# 03-ToF.net
KiCad netlist of a schematic drawn in EAGLE
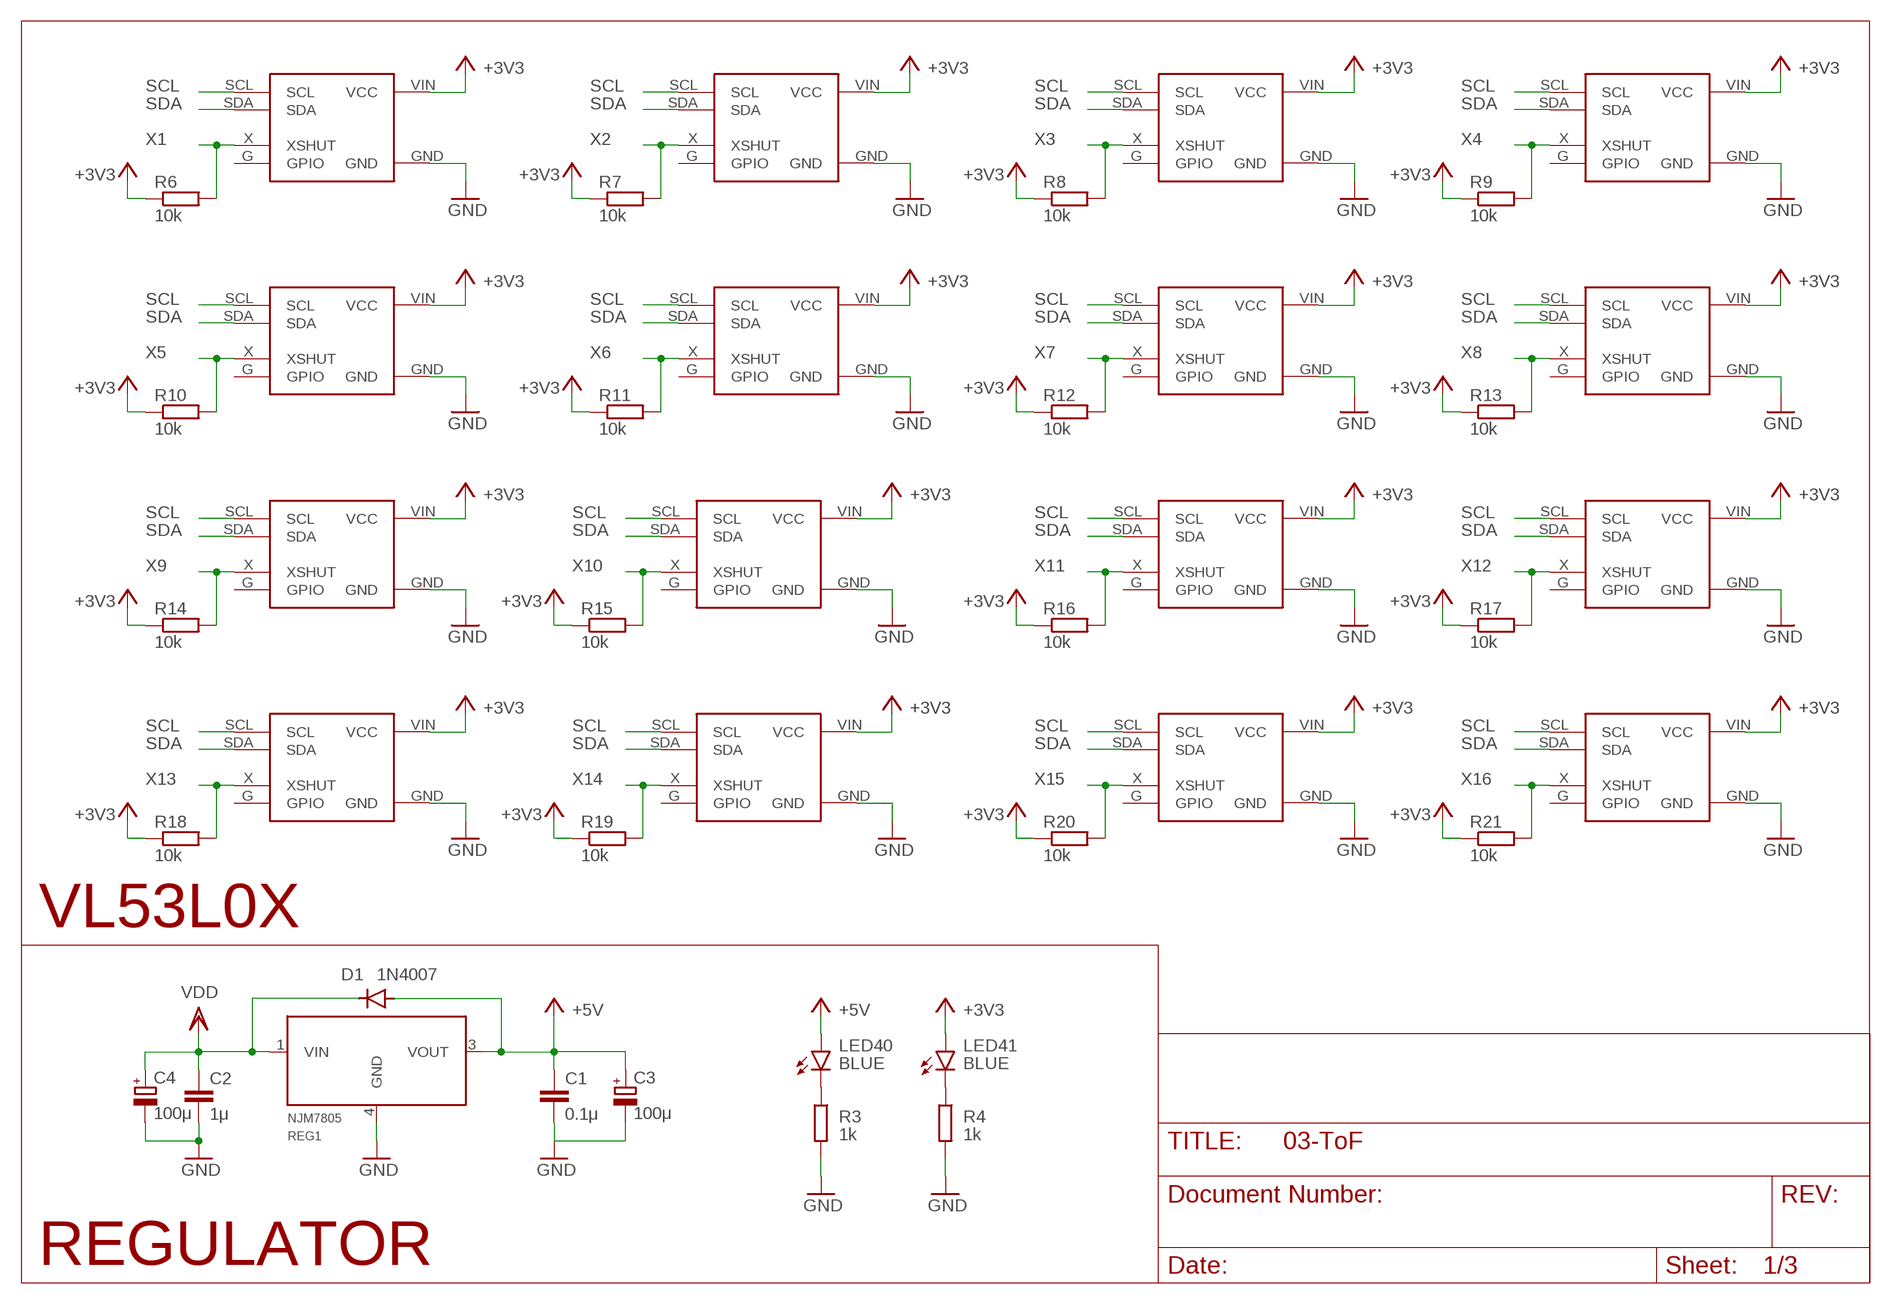
[diagram p0: schematic, sheet 1]
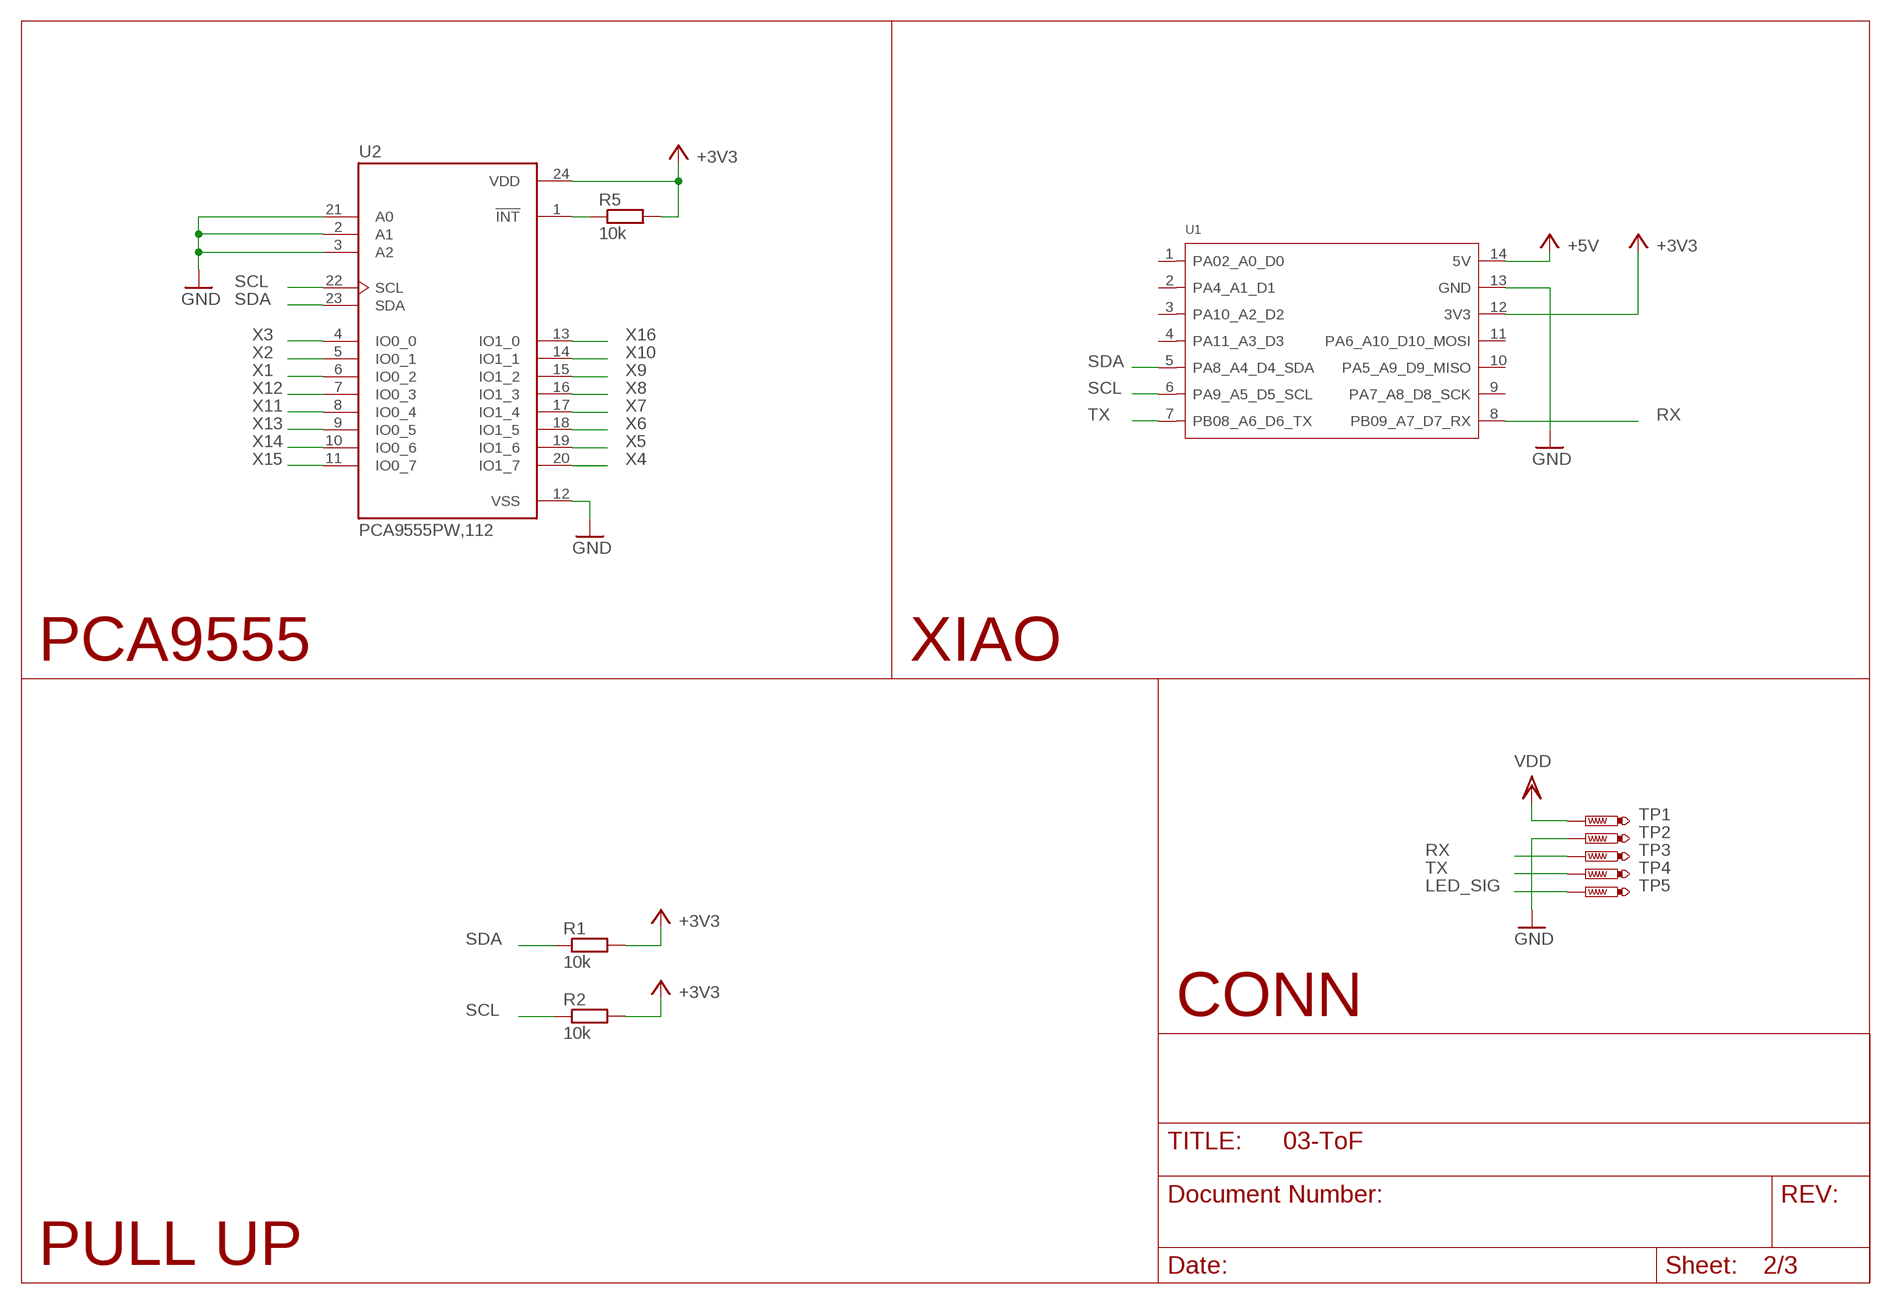
[diagram p1: schematic, sheet 2]
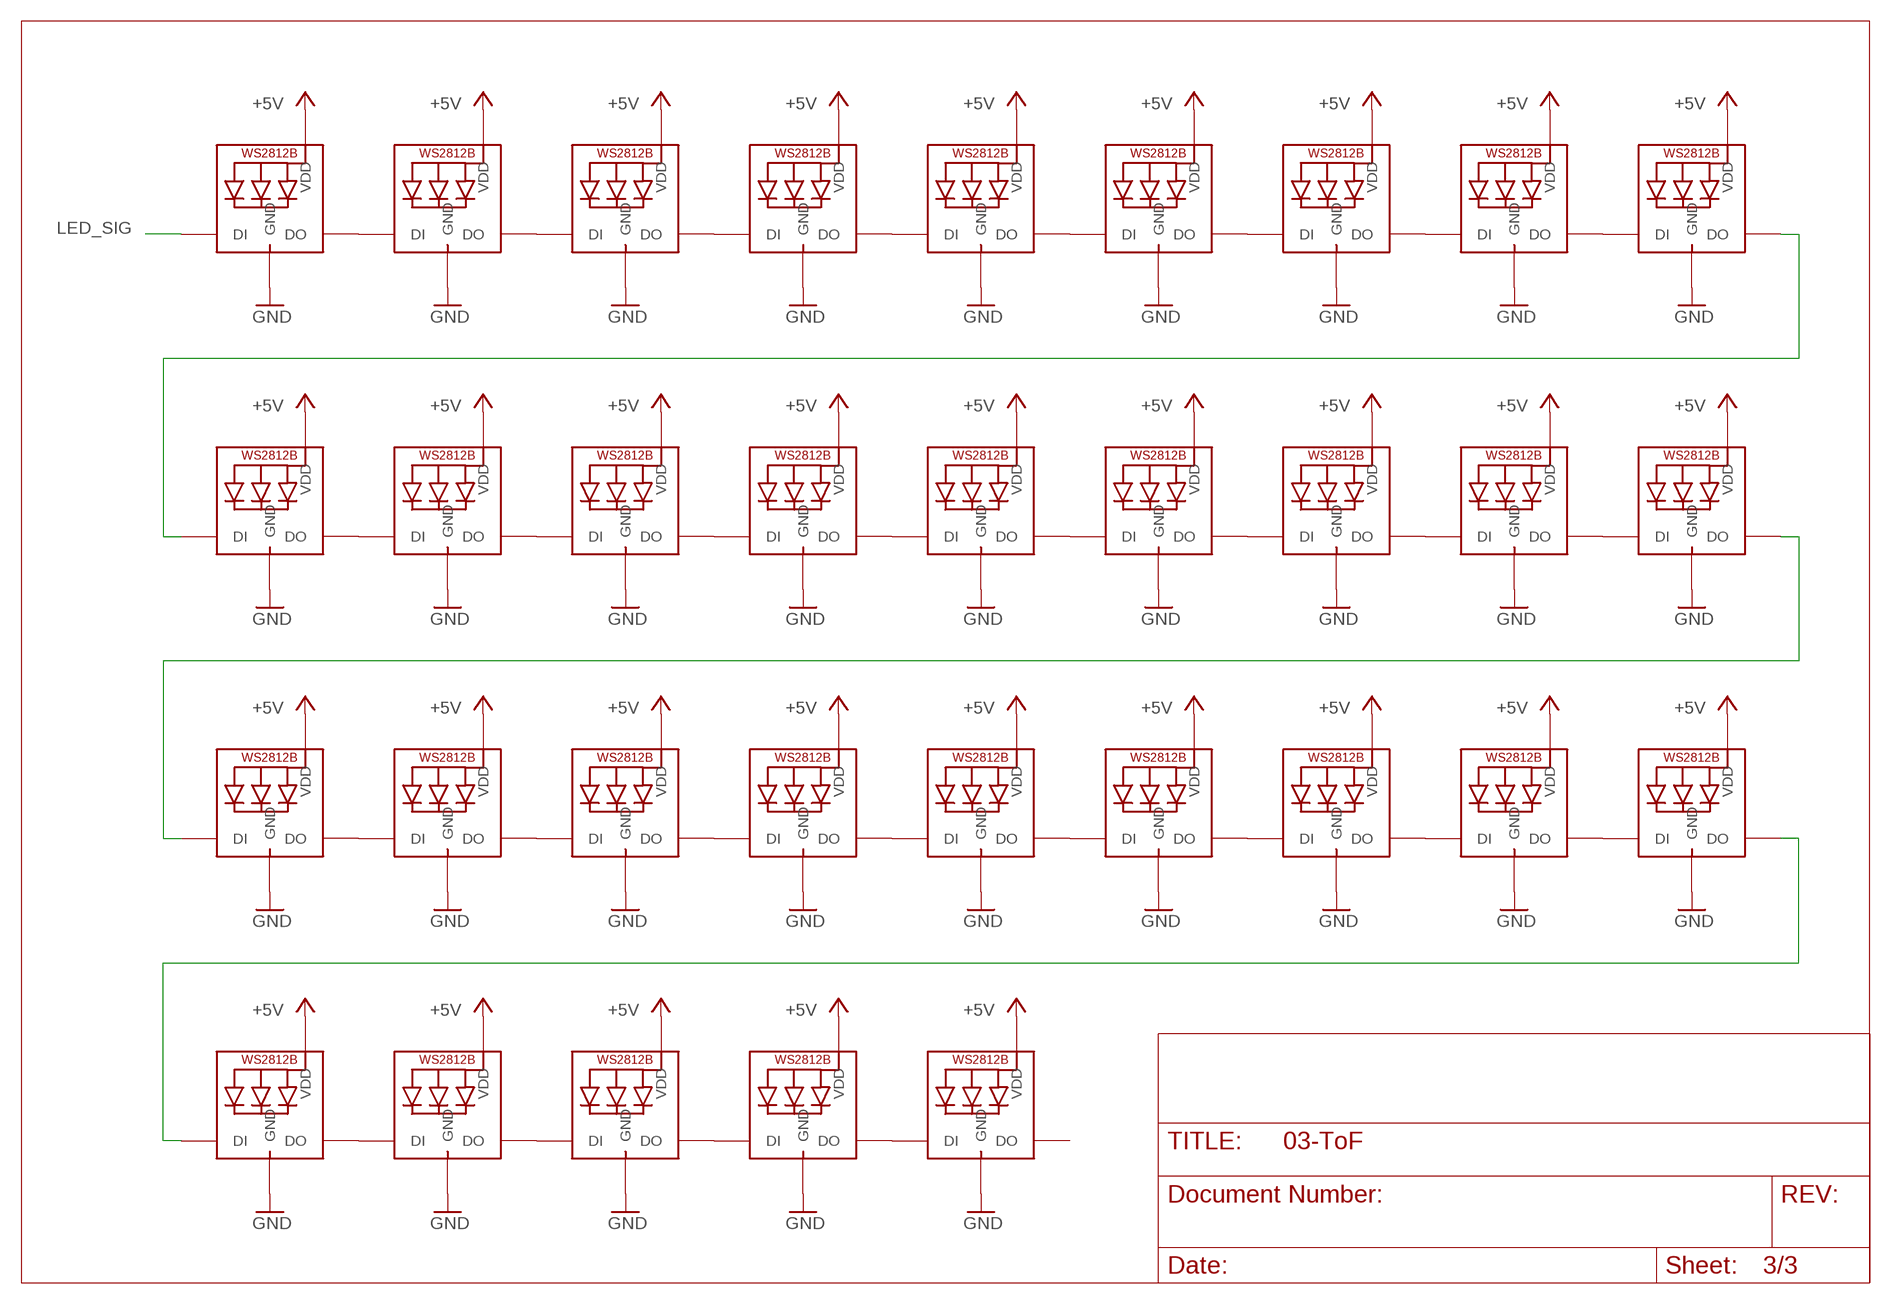
[diagram p2: schematic, sheet 3]

(export (version "E")
  (design (tool "Eeschema 10.0.6"))
  (components
    (comp (ref "LED1")
      (value "WS2812B_5050N")
      (footprint "eagle-import:WS2812B-NARROW")
      (libsource (lib "eagle-import") (part "WS2812B_5050N"))
    )
    (comp (ref "LED2")
      (value "WS2812B_5050N")
      (footprint "eagle-import:WS2812B-NARROW")
      (libsource (lib "eagle-import") (part "WS2812B_5050N"))
    )
    (comp (ref "LED3")
      (value "WS2812B_5050N")
      (footprint "eagle-import:WS2812B-NARROW")
      (libsource (lib "eagle-import") (part "WS2812B_5050N"))
    )
    (comp (ref "LED4")
      (value "WS2812B_5050N")
      (footprint "eagle-import:WS2812B-NARROW")
      (libsource (lib "eagle-import") (part "WS2812B_5050N"))
    )
    (comp (ref "LED5")
      (value "WS2812B_5050N")
      (footprint "eagle-import:WS2812B-NARROW")
      (libsource (lib "eagle-import") (part "WS2812B_5050N"))
    )
    (comp (ref "LED6")
      (value "WS2812B_5050N")
      (footprint "eagle-import:WS2812B-NARROW")
      (libsource (lib "eagle-import") (part "WS2812B_5050N"))
    )
    (comp (ref "LED7")
      (value "WS2812B_5050N")
      (footprint "eagle-import:WS2812B-NARROW")
      (libsource (lib "eagle-import") (part "WS2812B_5050N"))
    )
    (comp (ref "LED8")
      (value "WS2812B_5050N")
      (footprint "eagle-import:WS2812B-NARROW")
      (libsource (lib "eagle-import") (part "WS2812B_5050N"))
    )
    (comp (ref "LED9")
      (value "WS2812B_5050N")
      (footprint "eagle-import:WS2812B-NARROW")
      (libsource (lib "eagle-import") (part "WS2812B_5050N"))
    )
    (comp (ref "LED10")
      (value "WS2812B_5050N")
      (footprint "eagle-import:WS2812B-NARROW")
      (libsource (lib "eagle-import") (part "WS2812B_5050N"))
    )
    (comp (ref "LED11")
      (value "WS2812B_5050N")
      (footprint "eagle-import:WS2812B-NARROW")
      (libsource (lib "eagle-import") (part "WS2812B_5050N"))
    )
    (comp (ref "LED12")
      (value "WS2812B_5050N")
      (footprint "eagle-import:WS2812B-NARROW")
      (libsource (lib "eagle-import") (part "WS2812B_5050N"))
    )
    (comp (ref "LED13")
      (value "WS2812B_5050N")
      (footprint "eagle-import:WS2812B-NARROW")
      (libsource (lib "eagle-import") (part "WS2812B_5050N"))
    )
    (comp (ref "LED14")
      (value "WS2812B_5050N")
      (footprint "eagle-import:WS2812B-NARROW")
      (libsource (lib "eagle-import") (part "WS2812B_5050N"))
    )
    (comp (ref "LED15")
      (value "WS2812B_5050N")
      (footprint "eagle-import:WS2812B-NARROW")
      (libsource (lib "eagle-import") (part "WS2812B_5050N"))
    )
    (comp (ref "LED16")
      (value "WS2812B_5050N")
      (footprint "eagle-import:WS2812B-NARROW")
      (libsource (lib "eagle-import") (part "WS2812B_5050N"))
    )
    (comp (ref "LED17")
      (value "WS2812B_5050N")
      (footprint "eagle-import:WS2812B-NARROW")
      (libsource (lib "eagle-import") (part "WS2812B_5050N"))
    )
    (comp (ref "LED18")
      (value "WS2812B_5050N")
      (footprint "eagle-import:WS2812B-NARROW")
      (libsource (lib "eagle-import") (part "WS2812B_5050N"))
    )
    (comp (ref "LED19")
      (value "WS2812B_5050N")
      (footprint "eagle-import:WS2812B-NARROW")
      (libsource (lib "eagle-import") (part "WS2812B_5050N"))
    )
    (comp (ref "LED20")
      (value "WS2812B_5050N")
      (footprint "eagle-import:WS2812B-NARROW")
      (libsource (lib "eagle-import") (part "WS2812B_5050N"))
    )
    (comp (ref "LED21")
      (value "WS2812B_5050N")
      (footprint "eagle-import:WS2812B-NARROW")
      (libsource (lib "eagle-import") (part "WS2812B_5050N"))
    )
    (comp (ref "LED22")
      (value "WS2812B_5050N")
      (footprint "eagle-import:WS2812B-NARROW")
      (libsource (lib "eagle-import") (part "WS2812B_5050N"))
    )
    (comp (ref "LED23")
      (value "WS2812B_5050N")
      (footprint "eagle-import:WS2812B-NARROW")
      (libsource (lib "eagle-import") (part "WS2812B_5050N"))
    )
    (comp (ref "LED24")
      (value "WS2812B_5050N")
      (footprint "eagle-import:WS2812B-NARROW")
      (libsource (lib "eagle-import") (part "WS2812B_5050N"))
    )
    (comp (ref "LED25")
      (value "WS2812B_5050N")
      (footprint "eagle-import:WS2812B-NARROW")
      (libsource (lib "eagle-import") (part "WS2812B_5050N"))
    )
    (comp (ref "LED26")
      (value "WS2812B_5050N")
      (footprint "eagle-import:WS2812B-NARROW")
      (libsource (lib "eagle-import") (part "WS2812B_5050N"))
    )
    (comp (ref "LED27")
      (value "WS2812B_5050N")
      (footprint "eagle-import:WS2812B-NARROW")
      (libsource (lib "eagle-import") (part "WS2812B_5050N"))
    )
    (comp (ref "LED28")
      (value "WS2812B_5050N")
      (footprint "eagle-import:WS2812B-NARROW")
      (libsource (lib "eagle-import") (part "WS2812B_5050N"))
    )
    (comp (ref "LED29")
      (value "WS2812B_5050N")
      (footprint "eagle-import:WS2812B-NARROW")
      (libsource (lib "eagle-import") (part "WS2812B_5050N"))
    )
    (comp (ref "LED30")
      (value "WS2812B_5050N")
      (footprint "eagle-import:WS2812B-NARROW")
      (libsource (lib "eagle-import") (part "WS2812B_5050N"))
    )
    (comp (ref "LED31")
      (value "WS2812B_5050N")
      (footprint "eagle-import:WS2812B-NARROW")
      (libsource (lib "eagle-import") (part "WS2812B_5050N"))
    )
    (comp (ref "LED32")
      (value "WS2812B_5050N")
      (footprint "eagle-import:WS2812B-NARROW")
      (libsource (lib "eagle-import") (part "WS2812B_5050N"))
    )
    (comp (ref "C1")
      (value "0.1μ")
      (footprint "eagle-import:C0402")
      (libsource (lib "eagle-import") (part "C-EUC0402"))
    )
    (comp (ref "C2")
      (value "1μ")
      (footprint "eagle-import:C0402")
      (libsource (lib "eagle-import") (part "C-EUC0402"))
    )
    (comp (ref "C3")
      (value "100μ")
      (footprint "eagle-import:153CLV-0505")
      (libsource (lib "eagle-import") (part "CPOL-EU153CLV-0505"))
    )
    (comp (ref "C4")
      (value "100μ")
      (footprint "eagle-import:153CLV-0505")
      (libsource (lib "eagle-import") (part "CPOL-EU153CLV-0505"))
    )
    (comp (ref "D1")
      (value "1N4007")
      (footprint "eagle-import:SMA-DO214AC")
      (libsource (lib "eagle-import") (part "GF1"))
    )
    (comp (ref "LED40")
      (value "BLUE")
      (footprint "eagle-import:SML0603")
      (libsource (lib "eagle-import") (part "LEDSML0603"))
    )
    (comp (ref "LED41")
      (value "BLUE")
      (footprint "eagle-import:SML0603")
      (libsource (lib "eagle-import") (part "LEDSML0603"))
    )
    (comp (ref "R3")
      (value "1k")
      (footprint "eagle-import:R0402")
      (libsource (lib "eagle-import") (part "R-EU_R0402"))
    )
    (comp (ref "R4")
      (value "1k")
      (footprint "eagle-import:R0402")
      (libsource (lib "eagle-import") (part "R-EU_R0402"))
    )
    (comp (ref "R6")
      (value "10k")
      (footprint "eagle-import:R0402")
      (libsource (lib "eagle-import") (part "R-EU_R0402"))
    )
    (comp (ref "R7")
      (value "10k")
      (footprint "eagle-import:R0402")
      (libsource (lib "eagle-import") (part "R-EU_R0402"))
    )
    (comp (ref "R8")
      (value "10k")
      (footprint "eagle-import:R0402")
      (libsource (lib "eagle-import") (part "R-EU_R0402"))
    )
    (comp (ref "R9")
      (value "10k")
      (footprint "eagle-import:R0402")
      (libsource (lib "eagle-import") (part "R-EU_R0402"))
    )
    (comp (ref "R10")
      (value "10k")
      (footprint "eagle-import:R0402")
      (libsource (lib "eagle-import") (part "R-EU_R0402"))
    )
    (comp (ref "R11")
      (value "10k")
      (footprint "eagle-import:R0402")
      (libsource (lib "eagle-import") (part "R-EU_R0402"))
    )
    (comp (ref "R12")
      (value "10k")
      (footprint "eagle-import:R0402")
      (libsource (lib "eagle-import") (part "R-EU_R0402"))
    )
    (comp (ref "R13")
      (value "10k")
      (footprint "eagle-import:R0402")
      (libsource (lib "eagle-import") (part "R-EU_R0402"))
    )
    (comp (ref "R14")
      (value "10k")
      (footprint "eagle-import:R0402")
      (libsource (lib "eagle-import") (part "R-EU_R0402"))
    )
    (comp (ref "R15")
      (value "10k")
      (footprint "eagle-import:R0402")
      (libsource (lib "eagle-import") (part "R-EU_R0402"))
    )
    (comp (ref "R16")
      (value "10k")
      (footprint "eagle-import:R0402")
      (libsource (lib "eagle-import") (part "R-EU_R0402"))
    )
    (comp (ref "R17")
      (value "10k")
      (footprint "eagle-import:R0402")
      (libsource (lib "eagle-import") (part "R-EU_R0402"))
    )
    (comp (ref "R18")
      (value "10k")
      (footprint "eagle-import:R0402")
      (libsource (lib "eagle-import") (part "R-EU_R0402"))
    )
    (comp (ref "R19")
      (value "10k")
      (footprint "eagle-import:R0402")
      (libsource (lib "eagle-import") (part "R-EU_R0402"))
    )
    (comp (ref "R20")
      (value "10k")
      (footprint "eagle-import:R0402")
      (libsource (lib "eagle-import") (part "R-EU_R0402"))
    )
    (comp (ref "R21")
      (value "10k")
      (footprint "eagle-import:R0402")
      (libsource (lib "eagle-import") (part "R-EU_R0402"))
    )
    (comp (ref "REG1")
      (value "NJM7805")
      (footprint "eagle-import:MYPARTS_D-PAK_TO252AA")
      (libsource (lib "eagle-import") (part "MYPARTS_NJM7800S-REGULATOR"))
    )
    (comp (ref "VL1")
      (value "VL53L0X")
      (footprint "eagle-import:1X04")
      (libsource (lib "eagle-import") (part "VL53L0X"))
    )
    (comp (ref "VL2")
      (value "VL53L0X")
      (footprint "eagle-import:1X04")
      (libsource (lib "eagle-import") (part "VL53L0X"))
    )
    (comp (ref "VL3")
      (value "VL53L0X")
      (footprint "eagle-import:1X04")
      (libsource (lib "eagle-import") (part "VL53L0X"))
    )
    (comp (ref "VL4")
      (value "VL53L0X")
      (footprint "eagle-import:1X04")
      (libsource (lib "eagle-import") (part "VL53L0X"))
    )
    (comp (ref "VL5")
      (value "VL53L0X")
      (footprint "eagle-import:1X04")
      (libsource (lib "eagle-import") (part "VL53L0X"))
    )
    (comp (ref "VL6")
      (value "VL53L0X")
      (footprint "eagle-import:1X04")
      (libsource (lib "eagle-import") (part "VL53L0X"))
    )
    (comp (ref "VL7")
      (value "VL53L0X")
      (footprint "eagle-import:1X04")
      (libsource (lib "eagle-import") (part "VL53L0X"))
    )
    (comp (ref "VL8")
      (value "VL53L0X")
      (footprint "eagle-import:1X04")
      (libsource (lib "eagle-import") (part "VL53L0X"))
    )
    (comp (ref "VL9")
      (value "VL53L0X")
      (footprint "eagle-import:1X04")
      (libsource (lib "eagle-import") (part "VL53L0X"))
    )
    (comp (ref "VL10")
      (value "VL53L0X")
      (footprint "eagle-import:1X04")
      (libsource (lib "eagle-import") (part "VL53L0X"))
    )
    (comp (ref "VL11")
      (value "VL53L0X")
      (footprint "eagle-import:1X04")
      (libsource (lib "eagle-import") (part "VL53L0X"))
    )
    (comp (ref "VL12")
      (value "VL53L0X")
      (footprint "eagle-import:1X04")
      (libsource (lib "eagle-import") (part "VL53L0X"))
    )
    (comp (ref "VL13")
      (value "VL53L0X")
      (footprint "eagle-import:1X04")
      (libsource (lib "eagle-import") (part "VL53L0X"))
    )
    (comp (ref "VL14")
      (value "VL53L0X")
      (footprint "eagle-import:1X04")
      (libsource (lib "eagle-import") (part "VL53L0X"))
    )
    (comp (ref "VL15")
      (value "VL53L0X")
      (footprint "eagle-import:1X04")
      (libsource (lib "eagle-import") (part "VL53L0X"))
    )
    (comp (ref "VL16")
      (value "VL53L0X")
      (footprint "eagle-import:1X04")
      (libsource (lib "eagle-import") (part "VL53L0X"))
    )
    (comp (ref "R1")
      (value "10k")
      (footprint "eagle-import:R0402")
      (libsource (lib "eagle-import") (part "R-EU_R0402"))
    )
    (comp (ref "R2")
      (value "10k")
      (footprint "eagle-import:R0402")
      (libsource (lib "eagle-import") (part "R-EU_R0402"))
    )
    (comp (ref "R5")
      (value "10k")
      (footprint "eagle-import:R0402")
      (libsource (lib "eagle-import") (part "R-EU_R0402"))
    )
    (comp (ref "TP1")
      (value "PTR1TP10R")
      (footprint "eagle-import:TP10R")
      (libsource (lib "eagle-import") (part "PTR1TP10R"))
    )
    (comp (ref "TP2")
      (value "PTR1TP10SQ")
      (footprint "eagle-import:TP10SQ")
      (libsource (lib "eagle-import") (part "PTR1TP10SQ"))
    )
    (comp (ref "TP3")
      (value "PTR1TP10R")
      (footprint "eagle-import:TP10R")
      (libsource (lib "eagle-import") (part "PTR1TP10R"))
    )
    (comp (ref "TP4")
      (value "PTR1TP10R")
      (footprint "eagle-import:TP10R")
      (libsource (lib "eagle-import") (part "PTR1TP10R"))
    )
    (comp (ref "TP5")
      (value "PTR1TP10R")
      (footprint "eagle-import:TP10R")
      (libsource (lib "eagle-import") (part "PTR1TP10R"))
    )
    (comp (ref "U1")
      (value "MOUDLE-SEEEDUINO-XIAO")
      (footprint "eagle-import:MOUDLE14P-2.54-21X17.8MM")
      (libsource (lib "eagle-import") (part "MOUDLE-SEEEDUINO-XIAO"))
    )
    (comp (ref "U2")
      (value "PCA9555PW,112")
      (footprint "eagle-import:SOP65P640X110-24N")
      (fields (field (name "MF") "NXP Semiconductors"))
      (libsource (lib "eagle-import") (part "PCA9555PW,112"))
    )
  )
  (nets
    (net (code "1") (name "+3V3") (class "Default")
      (node (ref "LED41") (pin "A") (pinfunction "A_A") (pintype "passive"))
      (node (ref "R1") (pin "2") (pinfunction "2_2") (pintype "passive"))
      (node (ref "R10") (pin "1") (pinfunction "1_1") (pintype "passive"))
      (node (ref "R11") (pin "1") (pinfunction "1_1") (pintype "passive"))
      (node (ref "R12") (pin "1") (pinfunction "1_1") (pintype "passive"))
      (node (ref "R13") (pin "1") (pinfunction "1_1") (pintype "passive"))
      (node (ref "R14") (pin "1") (pinfunction "1_1") (pintype "passive"))
      (node (ref "R15") (pin "1") (pinfunction "1_1") (pintype "passive"))
      (node (ref "R16") (pin "1") (pinfunction "1_1") (pintype "passive"))
      (node (ref "R17") (pin "1") (pinfunction "1_1") (pintype "passive"))
      (node (ref "R18") (pin "1") (pinfunction "1_1") (pintype "passive"))
      (node (ref "R19") (pin "1") (pinfunction "1_1") (pintype "passive"))
      (node (ref "R2") (pin "2") (pinfunction "2_2") (pintype "passive"))
      (node (ref "R20") (pin "1") (pinfunction "1_1") (pintype "passive"))
      (node (ref "R21") (pin "1") (pinfunction "1_1") (pintype "passive"))
      (node (ref "R5") (pin "2") (pinfunction "2_2") (pintype "passive"))
      (node (ref "R6") (pin "1") (pinfunction "1_1") (pintype "passive"))
      (node (ref "R7") (pin "1") (pinfunction "1_1") (pintype "passive"))
      (node (ref "R8") (pin "1") (pinfunction "1_1") (pintype "passive"))
      (node (ref "R9") (pin "1") (pinfunction "1_1") (pintype "passive"))
      (node (ref "U1") (pin "12") (pinfunction "3V3_12") (pintype "bidirectional"))
      (node (ref "U2") (pin "24") (pinfunction "VDD_24") (pintype "power_in"))
      (node (ref "VL1") (pin "VIN") (pinfunction "VCC_VIN") (pintype "bidirectional"))
      (node (ref "VL10") (pin "VIN") (pinfunction "VCC_VIN") (pintype "bidirectional"))
      (node (ref "VL11") (pin "VIN") (pinfunction "VCC_VIN") (pintype "bidirectional"))
      (node (ref "VL12") (pin "VIN") (pinfunction "VCC_VIN") (pintype "bidirectional"))
      (node (ref "VL13") (pin "VIN") (pinfunction "VCC_VIN") (pintype "bidirectional"))
      (node (ref "VL14") (pin "VIN") (pinfunction "VCC_VIN") (pintype "bidirectional"))
      (node (ref "VL15") (pin "VIN") (pinfunction "VCC_VIN") (pintype "bidirectional"))
      (node (ref "VL16") (pin "VIN") (pinfunction "VCC_VIN") (pintype "bidirectional"))
      (node (ref "VL2") (pin "VIN") (pinfunction "VCC_VIN") (pintype "bidirectional"))
      (node (ref "VL3") (pin "VIN") (pinfunction "VCC_VIN") (pintype "bidirectional"))
      (node (ref "VL4") (pin "VIN") (pinfunction "VCC_VIN") (pintype "bidirectional"))
      (node (ref "VL5") (pin "VIN") (pinfunction "VCC_VIN") (pintype "bidirectional"))
      (node (ref "VL6") (pin "VIN") (pinfunction "VCC_VIN") (pintype "bidirectional"))
      (node (ref "VL7") (pin "VIN") (pinfunction "VCC_VIN") (pintype "bidirectional"))
      (node (ref "VL8") (pin "VIN") (pinfunction "VCC_VIN") (pintype "bidirectional"))
      (node (ref "VL9") (pin "VIN") (pinfunction "VCC_VIN") (pintype "bidirectional"))
    )
    (net (code "2") (name "+5V") (class "Default")
      (node (ref "C1") (pin "1") (pinfunction "1_1") (pintype "passive"))
      (node (ref "C3") (pin "+") (pinfunction "+_+") (pintype "passive"))
      (node (ref "D1") (pin "A") (pinfunction "A_A") (pintype "passive"))
      (node (ref "LED1") (pin "1-VDD") (pinfunction "VDD_1-VDD") (pintype "power_in"))
      (node (ref "LED10") (pin "1-VDD") (pinfunction "VDD_1-VDD") (pintype "power_in"))
      (node (ref "LED11") (pin "1-VDD") (pinfunction "VDD_1-VDD") (pintype "power_in"))
      (node (ref "LED12") (pin "1-VDD") (pinfunction "VDD_1-VDD") (pintype "power_in"))
      (node (ref "LED13") (pin "1-VDD") (pinfunction "VDD_1-VDD") (pintype "power_in"))
      (node (ref "LED14") (pin "1-VDD") (pinfunction "VDD_1-VDD") (pintype "power_in"))
      (node (ref "LED15") (pin "1-VDD") (pinfunction "VDD_1-VDD") (pintype "power_in"))
      (node (ref "LED16") (pin "1-VDD") (pinfunction "VDD_1-VDD") (pintype "power_in"))
      (node (ref "LED17") (pin "1-VDD") (pinfunction "VDD_1-VDD") (pintype "power_in"))
      (node (ref "LED18") (pin "1-VDD") (pinfunction "VDD_1-VDD") (pintype "power_in"))
      (node (ref "LED19") (pin "1-VDD") (pinfunction "VDD_1-VDD") (pintype "power_in"))
      (node (ref "LED2") (pin "1-VDD") (pinfunction "VDD_1-VDD") (pintype "power_in"))
      (node (ref "LED20") (pin "1-VDD") (pinfunction "VDD_1-VDD") (pintype "power_in"))
      (node (ref "LED21") (pin "1-VDD") (pinfunction "VDD_1-VDD") (pintype "power_in"))
      (node (ref "LED22") (pin "1-VDD") (pinfunction "VDD_1-VDD") (pintype "power_in"))
      (node (ref "LED23") (pin "1-VDD") (pinfunction "VDD_1-VDD") (pintype "power_in"))
      (node (ref "LED24") (pin "1-VDD") (pinfunction "VDD_1-VDD") (pintype "power_in"))
      (node (ref "LED25") (pin "1-VDD") (pinfunction "VDD_1-VDD") (pintype "power_in"))
      (node (ref "LED26") (pin "1-VDD") (pinfunction "VDD_1-VDD") (pintype "power_in"))
      (node (ref "LED27") (pin "1-VDD") (pinfunction "VDD_1-VDD") (pintype "power_in"))
      (node (ref "LED28") (pin "1-VDD") (pinfunction "VDD_1-VDD") (pintype "power_in"))
      (node (ref "LED29") (pin "1-VDD") (pinfunction "VDD_1-VDD") (pintype "power_in"))
      (node (ref "LED3") (pin "1-VDD") (pinfunction "VDD_1-VDD") (pintype "power_in"))
      (node (ref "LED30") (pin "1-VDD") (pinfunction "VDD_1-VDD") (pintype "power_in"))
      (node (ref "LED31") (pin "1-VDD") (pinfunction "VDD_1-VDD") (pintype "power_in"))
      (node (ref "LED32") (pin "1-VDD") (pinfunction "VDD_1-VDD") (pintype "power_in"))
      (node (ref "LED4") (pin "1-VDD") (pinfunction "VDD_1-VDD") (pintype "power_in"))
      (node (ref "LED40") (pin "A") (pinfunction "A_A") (pintype "passive"))
      (node (ref "LED5") (pin "1-VDD") (pinfunction "VDD_1-VDD") (pintype "power_in"))
      (node (ref "LED6") (pin "1-VDD") (pinfunction "VDD_1-VDD") (pintype "power_in"))
      (node (ref "LED7") (pin "1-VDD") (pinfunction "VDD_1-VDD") (pintype "power_in"))
      (node (ref "LED8") (pin "1-VDD") (pinfunction "VDD_1-VDD") (pintype "power_in"))
      (node (ref "LED9") (pin "1-VDD") (pinfunction "VDD_1-VDD") (pintype "power_in"))
      (node (ref "REG1") (pin "3") (pinfunction "VOUT_3") (pintype "passive"))
      (node (ref "U1") (pin "14") (pinfunction "5V_14") (pintype "bidirectional"))
    )
    (net (code "3") (name "GND") (class "Default")
      (node (ref "C1") (pin "2") (pinfunction "2_2") (pintype "passive"))
      (node (ref "C2") (pin "2") (pinfunction "2_2") (pintype "passive"))
      (node (ref "C3") (pin "-") (pinfunction "-_-") (pintype "passive"))
      (node (ref "C4") (pin "-") (pinfunction "-_-") (pintype "passive"))
      (node (ref "LED1") (pin "3-GND") (pinfunction "GND_3-GND") (pintype "power_in"))
      (node (ref "LED10") (pin "3-GND") (pinfunction "GND_3-GND") (pintype "power_in"))
      (node (ref "LED11") (pin "3-GND") (pinfunction "GND_3-GND") (pintype "power_in"))
      (node (ref "LED12") (pin "3-GND") (pinfunction "GND_3-GND") (pintype "power_in"))
      (node (ref "LED13") (pin "3-GND") (pinfunction "GND_3-GND") (pintype "power_in"))
      (node (ref "LED14") (pin "3-GND") (pinfunction "GND_3-GND") (pintype "power_in"))
      (node (ref "LED15") (pin "3-GND") (pinfunction "GND_3-GND") (pintype "power_in"))
      (node (ref "LED16") (pin "3-GND") (pinfunction "GND_3-GND") (pintype "power_in"))
      (node (ref "LED17") (pin "3-GND") (pinfunction "GND_3-GND") (pintype "power_in"))
      (node (ref "LED18") (pin "3-GND") (pinfunction "GND_3-GND") (pintype "power_in"))
      (node (ref "LED19") (pin "3-GND") (pinfunction "GND_3-GND") (pintype "power_in"))
      (node (ref "LED2") (pin "3-GND") (pinfunction "GND_3-GND") (pintype "power_in"))
      (node (ref "LED20") (pin "3-GND") (pinfunction "GND_3-GND") (pintype "power_in"))
      (node (ref "LED21") (pin "3-GND") (pinfunction "GND_3-GND") (pintype "power_in"))
      (node (ref "LED22") (pin "3-GND") (pinfunction "GND_3-GND") (pintype "power_in"))
      (node (ref "LED23") (pin "3-GND") (pinfunction "GND_3-GND") (pintype "power_in"))
      (node (ref "LED24") (pin "3-GND") (pinfunction "GND_3-GND") (pintype "power_in"))
      (node (ref "LED25") (pin "3-GND") (pinfunction "GND_3-GND") (pintype "power_in"))
      (node (ref "LED26") (pin "3-GND") (pinfunction "GND_3-GND") (pintype "power_in"))
      (node (ref "LED27") (pin "3-GND") (pinfunction "GND_3-GND") (pintype "power_in"))
      (node (ref "LED28") (pin "3-GND") (pinfunction "GND_3-GND") (pintype "power_in"))
      (node (ref "LED29") (pin "3-GND") (pinfunction "GND_3-GND") (pintype "power_in"))
      (node (ref "LED3") (pin "3-GND") (pinfunction "GND_3-GND") (pintype "power_in"))
      (node (ref "LED30") (pin "3-GND") (pinfunction "GND_3-GND") (pintype "power_in"))
      (node (ref "LED31") (pin "3-GND") (pinfunction "GND_3-GND") (pintype "power_in"))
      (node (ref "LED32") (pin "3-GND") (pinfunction "GND_3-GND") (pintype "power_in"))
      (node (ref "LED4") (pin "3-GND") (pinfunction "GND_3-GND") (pintype "power_in"))
      (node (ref "LED5") (pin "3-GND") (pinfunction "GND_3-GND") (pintype "power_in"))
      (node (ref "LED6") (pin "3-GND") (pinfunction "GND_3-GND") (pintype "power_in"))
      (node (ref "LED7") (pin "3-GND") (pinfunction "GND_3-GND") (pintype "power_in"))
      (node (ref "LED8") (pin "3-GND") (pinfunction "GND_3-GND") (pintype "power_in"))
      (node (ref "LED9") (pin "3-GND") (pinfunction "GND_3-GND") (pintype "power_in"))
      (node (ref "R3") (pin "2") (pinfunction "2_2") (pintype "passive"))
      (node (ref "R4") (pin "2") (pinfunction "2_2") (pintype "passive"))
      (node (ref "REG1") (pin "4") (pinfunction "GND_4") (pintype "passive"))
      (node (ref "TP2") (pin "TP") (pinfunction "TP_TP") (pintype "input"))
      (node (ref "U1") (pin "13") (pinfunction "GND_13") (pintype "bidirectional"))
      (node (ref "U2") (pin "12") (pinfunction "VSS_12") (pintype "power_in"))
      (node (ref "U2") (pin "2") (pinfunction "A1_2") (pintype "input"))
      (node (ref "U2") (pin "21") (pinfunction "A0_21") (pintype "input"))
      (node (ref "U2") (pin "3") (pinfunction "A2_3") (pintype "input"))
      (node (ref "VL1") (pin "GND") (pinfunction "GND_GND") (pintype "bidirectional"))
      (node (ref "VL10") (pin "GND") (pinfunction "GND_GND") (pintype "bidirectional"))
      (node (ref "VL11") (pin "GND") (pinfunction "GND_GND") (pintype "bidirectional"))
      (node (ref "VL12") (pin "GND") (pinfunction "GND_GND") (pintype "bidirectional"))
      (node (ref "VL13") (pin "GND") (pinfunction "GND_GND") (pintype "bidirectional"))
      (node (ref "VL14") (pin "GND") (pinfunction "GND_GND") (pintype "bidirectional"))
      (node (ref "VL15") (pin "GND") (pinfunction "GND_GND") (pintype "bidirectional"))
      (node (ref "VL16") (pin "GND") (pinfunction "GND_GND") (pintype "bidirectional"))
      (node (ref "VL2") (pin "GND") (pinfunction "GND_GND") (pintype "bidirectional"))
      (node (ref "VL3") (pin "GND") (pinfunction "GND_GND") (pintype "bidirectional"))
      (node (ref "VL4") (pin "GND") (pinfunction "GND_GND") (pintype "bidirectional"))
      (node (ref "VL5") (pin "GND") (pinfunction "GND_GND") (pintype "bidirectional"))
      (node (ref "VL6") (pin "GND") (pinfunction "GND_GND") (pintype "bidirectional"))
      (node (ref "VL7") (pin "GND") (pinfunction "GND_GND") (pintype "bidirectional"))
      (node (ref "VL8") (pin "GND") (pinfunction "GND_GND") (pintype "bidirectional"))
      (node (ref "VL9") (pin "GND") (pinfunction "GND_GND") (pintype "bidirectional"))
    )
    (net (code "4") (name "LED_SIG") (class "Default")
      (node (ref "LED1") (pin "4-DIN") (pinfunction "DI_4-DIN") (pintype "input"))
      (node (ref "TP5") (pin "TP") (pinfunction "TP_TP") (pintype "input"))
    )
    (net (code "5") (name "Net-(LED1-DO)") (class "Default")
      (node (ref "LED1") (pin "2-DOUT") (pinfunction "DO_2-DOUT") (pintype "output"))
      (node (ref "LED2") (pin "4-DIN") (pinfunction "DI_4-DIN") (pintype "input"))
    )
    (net (code "6") (name "Net-(LED2-DO)") (class "Default")
      (node (ref "LED2") (pin "2-DOUT") (pinfunction "DO_2-DOUT") (pintype "output"))
      (node (ref "LED3") (pin "4-DIN") (pinfunction "DI_4-DIN") (pintype "input"))
    )
    (net (code "7") (name "Net-(LED3-DO)") (class "Default")
      (node (ref "LED3") (pin "2-DOUT") (pinfunction "DO_2-DOUT") (pintype "output"))
      (node (ref "LED4") (pin "4-DIN") (pinfunction "DI_4-DIN") (pintype "input"))
    )
    (net (code "8") (name "Net-(LED4-DO)") (class "Default")
      (node (ref "LED4") (pin "2-DOUT") (pinfunction "DO_2-DOUT") (pintype "output"))
      (node (ref "LED5") (pin "4-DIN") (pinfunction "DI_4-DIN") (pintype "input"))
    )
    (net (code "9") (name "Net-(LED5-DO)") (class "Default")
      (node (ref "LED5") (pin "2-DOUT") (pinfunction "DO_2-DOUT") (pintype "output"))
      (node (ref "LED6") (pin "4-DIN") (pinfunction "DI_4-DIN") (pintype "input"))
    )
    (net (code "10") (name "Net-(LED6-DO)") (class "Default")
      (node (ref "LED6") (pin "2-DOUT") (pinfunction "DO_2-DOUT") (pintype "output"))
      (node (ref "LED7") (pin "4-DIN") (pinfunction "DI_4-DIN") (pintype "input"))
    )
    (net (code "11") (name "Net-(LED7-DO)") (class "Default")
      (node (ref "LED7") (pin "2-DOUT") (pinfunction "DO_2-DOUT") (pintype "output"))
      (node (ref "LED8") (pin "4-DIN") (pinfunction "DI_4-DIN") (pintype "input"))
    )
    (net (code "12") (name "Net-(LED8-DO)") (class "Default")
      (node (ref "LED8") (pin "2-DOUT") (pinfunction "DO_2-DOUT") (pintype "output"))
      (node (ref "LED9") (pin "4-DIN") (pinfunction "DI_4-DIN") (pintype "input"))
    )
    (net (code "13") (name "Net-(LED10-DI)") (class "Default")
      (node (ref "LED10") (pin "4-DIN") (pinfunction "DI_4-DIN") (pintype "input"))
      (node (ref "LED9") (pin "2-DOUT") (pinfunction "DO_2-DOUT") (pintype "output"))
    )
    (net (code "14") (name "Net-(LED10-DO)") (class "Default")
      (node (ref "LED10") (pin "2-DOUT") (pinfunction "DO_2-DOUT") (pintype "output"))
      (node (ref "LED11") (pin "4-DIN") (pinfunction "DI_4-DIN") (pintype "input"))
    )
    (net (code "15") (name "Net-(LED11-DO)") (class "Default")
      (node (ref "LED11") (pin "2-DOUT") (pinfunction "DO_2-DOUT") (pintype "output"))
      (node (ref "LED12") (pin "4-DIN") (pinfunction "DI_4-DIN") (pintype "input"))
    )
    (net (code "16") (name "Net-(LED12-DO)") (class "Default")
      (node (ref "LED12") (pin "2-DOUT") (pinfunction "DO_2-DOUT") (pintype "output"))
      (node (ref "LED13") (pin "4-DIN") (pinfunction "DI_4-DIN") (pintype "input"))
    )
    (net (code "17") (name "Net-(LED13-DO)") (class "Default")
      (node (ref "LED13") (pin "2-DOUT") (pinfunction "DO_2-DOUT") (pintype "output"))
      (node (ref "LED14") (pin "4-DIN") (pinfunction "DI_4-DIN") (pintype "input"))
    )
    (net (code "18") (name "Net-(LED14-DO)") (class "Default")
      (node (ref "LED14") (pin "2-DOUT") (pinfunction "DO_2-DOUT") (pintype "output"))
      (node (ref "LED15") (pin "4-DIN") (pinfunction "DI_4-DIN") (pintype "input"))
    )
    (net (code "19") (name "Net-(LED15-DO)") (class "Default")
      (node (ref "LED15") (pin "2-DOUT") (pinfunction "DO_2-DOUT") (pintype "output"))
      (node (ref "LED16") (pin "4-DIN") (pinfunction "DI_4-DIN") (pintype "input"))
    )
    (net (code "20") (name "Net-(LED16-DO)") (class "Default")
      (node (ref "LED16") (pin "2-DOUT") (pinfunction "DO_2-DOUT") (pintype "output"))
      (node (ref "LED17") (pin "4-DIN") (pinfunction "DI_4-DIN") (pintype "input"))
    )
    (net (code "21") (name "Net-(LED17-DO)") (class "Default")
      (node (ref "LED17") (pin "2-DOUT") (pinfunction "DO_2-DOUT") (pintype "output"))
      (node (ref "LED18") (pin "4-DIN") (pinfunction "DI_4-DIN") (pintype "input"))
    )
    (net (code "22") (name "Net-(LED18-DO)") (class "Default")
      (node (ref "LED18") (pin "2-DOUT") (pinfunction "DO_2-DOUT") (pintype "output"))
      (node (ref "LED19") (pin "4-DIN") (pinfunction "DI_4-DIN") (pintype "input"))
    )
    (net (code "23") (name "Net-(LED19-DO)") (class "Default")
      (node (ref "LED19") (pin "2-DOUT") (pinfunction "DO_2-DOUT") (pintype "output"))
      (node (ref "LED20") (pin "4-DIN") (pinfunction "DI_4-DIN") (pintype "input"))
    )
    (net (code "24") (name "Net-(LED20-DO)") (class "Default")
      (node (ref "LED20") (pin "2-DOUT") (pinfunction "DO_2-DOUT") (pintype "output"))
      (node (ref "LED21") (pin "4-DIN") (pinfunction "DI_4-DIN") (pintype "input"))
    )
    (net (code "25") (name "Net-(LED21-DO)") (class "Default")
      (node (ref "LED21") (pin "2-DOUT") (pinfunction "DO_2-DOUT") (pintype "output"))
      (node (ref "LED22") (pin "4-DIN") (pinfunction "DI_4-DIN") (pintype "input"))
    )
    (net (code "26") (name "Net-(LED22-DO)") (class "Default")
      (node (ref "LED22") (pin "2-DOUT") (pinfunction "DO_2-DOUT") (pintype "output"))
      (node (ref "LED23") (pin "4-DIN") (pinfunction "DI_4-DIN") (pintype "input"))
    )
    (net (code "27") (name "Net-(LED23-DO)") (class "Default")
      (node (ref "LED23") (pin "2-DOUT") (pinfunction "DO_2-DOUT") (pintype "output"))
      (node (ref "LED24") (pin "4-DIN") (pinfunction "DI_4-DIN") (pintype "input"))
    )
    (net (code "28") (name "Net-(LED24-DO)") (class "Default")
      (node (ref "LED24") (pin "2-DOUT") (pinfunction "DO_2-DOUT") (pintype "output"))
      (node (ref "LED25") (pin "4-DIN") (pinfunction "DI_4-DIN") (pintype "input"))
    )
    (net (code "29") (name "Net-(LED25-DO)") (class "Default")
      (node (ref "LED25") (pin "2-DOUT") (pinfunction "DO_2-DOUT") (pintype "output"))
      (node (ref "LED26") (pin "4-DIN") (pinfunction "DI_4-DIN") (pintype "input"))
    )
    (net (code "30") (name "Net-(LED26-DO)") (class "Default")
      (node (ref "LED26") (pin "2-DOUT") (pinfunction "DO_2-DOUT") (pintype "output"))
      (node (ref "LED27") (pin "4-DIN") (pinfunction "DI_4-DIN") (pintype "input"))
    )
    (net (code "31") (name "Net-(LED27-DO)") (class "Default")
      (node (ref "LED27") (pin "2-DOUT") (pinfunction "DO_2-DOUT") (pintype "output"))
      (node (ref "LED28") (pin "4-DIN") (pinfunction "DI_4-DIN") (pintype "input"))
    )
    (net (code "32") (name "Net-(LED28-DO)") (class "Default")
      (node (ref "LED28") (pin "2-DOUT") (pinfunction "DO_2-DOUT") (pintype "output"))
      (node (ref "LED29") (pin "4-DIN") (pinfunction "DI_4-DIN") (pintype "input"))
    )
    (net (code "33") (name "Net-(LED29-DO)") (class "Default")
      (node (ref "LED29") (pin "2-DOUT") (pinfunction "DO_2-DOUT") (pintype "output"))
      (node (ref "LED30") (pin "4-DIN") (pinfunction "DI_4-DIN") (pintype "input"))
    )
    (net (code "34") (name "Net-(LED30-DO)") (class "Default")
      (node (ref "LED30") (pin "2-DOUT") (pinfunction "DO_2-DOUT") (pintype "output"))
      (node (ref "LED31") (pin "4-DIN") (pinfunction "DI_4-DIN") (pintype "input"))
    )
    (net (code "35") (name "Net-(LED31-DO)") (class "Default")
      (node (ref "LED31") (pin "2-DOUT") (pinfunction "DO_2-DOUT") (pintype "output"))
      (node (ref "LED32") (pin "4-DIN") (pinfunction "DI_4-DIN") (pintype "input"))
    )
    (net (code "36") (name "Net-(LED40-PadC)") (class "Default")
      (node (ref "LED40") (pin "C") (pinfunction "C_C") (pintype "passive"))
      (node (ref "R3") (pin "1") (pinfunction "1_1") (pintype "passive"))
    )
    (net (code "37") (name "Net-(LED41-PadC)") (class "Default")
      (node (ref "LED41") (pin "C") (pinfunction "C_C") (pintype "passive"))
      (node (ref "R4") (pin "1") (pinfunction "1_1") (pintype "passive"))
    )
    (net (code "38") (name "Net-(U2-~{INT})") (class "Default")
      (node (ref "R5") (pin "1") (pinfunction "1_1") (pintype "passive"))
      (node (ref "U2") (pin "1") (pinfunction "~{INT}_1") (pintype "output"))
    )
    (net (code "39") (name "RX") (class "Default")
      (node (ref "TP3") (pin "TP") (pinfunction "TP_TP") (pintype "input"))
      (node (ref "U1") (pin "8") (pinfunction "PB09_A7_D7_RX_8") (pintype "bidirectional"))
    )
    (net (code "40") (name "SCL") (class "Default")
      (node (ref "R2") (pin "1") (pinfunction "1_1") (pintype "passive"))
      (node (ref "U1") (pin "6") (pinfunction "PA9_A5_D5_SCL_6") (pintype "bidirectional"))
      (node (ref "U2") (pin "22") (pinfunction "SCL_22") (pintype "input"))
      (node (ref "VL1") (pin "SCL") (pinfunction "SCL_SCL") (pintype "bidirectional"))
      (node (ref "VL10") (pin "SCL") (pinfunction "SCL_SCL") (pintype "bidirectional"))
      (node (ref "VL11") (pin "SCL") (pinfunction "SCL_SCL") (pintype "bidirectional"))
      (node (ref "VL12") (pin "SCL") (pinfunction "SCL_SCL") (pintype "bidirectional"))
      (node (ref "VL13") (pin "SCL") (pinfunction "SCL_SCL") (pintype "bidirectional"))
      (node (ref "VL14") (pin "SCL") (pinfunction "SCL_SCL") (pintype "bidirectional"))
      (node (ref "VL15") (pin "SCL") (pinfunction "SCL_SCL") (pintype "bidirectional"))
      (node (ref "VL16") (pin "SCL") (pinfunction "SCL_SCL") (pintype "bidirectional"))
      (node (ref "VL2") (pin "SCL") (pinfunction "SCL_SCL") (pintype "bidirectional"))
      (node (ref "VL3") (pin "SCL") (pinfunction "SCL_SCL") (pintype "bidirectional"))
      (node (ref "VL4") (pin "SCL") (pinfunction "SCL_SCL") (pintype "bidirectional"))
      (node (ref "VL5") (pin "SCL") (pinfunction "SCL_SCL") (pintype "bidirectional"))
      (node (ref "VL6") (pin "SCL") (pinfunction "SCL_SCL") (pintype "bidirectional"))
      (node (ref "VL7") (pin "SCL") (pinfunction "SCL_SCL") (pintype "bidirectional"))
      (node (ref "VL8") (pin "SCL") (pinfunction "SCL_SCL") (pintype "bidirectional"))
      (node (ref "VL9") (pin "SCL") (pinfunction "SCL_SCL") (pintype "bidirectional"))
    )
    (net (code "41") (name "SDA") (class "Default")
      (node (ref "R1") (pin "1") (pinfunction "1_1") (pintype "passive"))
      (node (ref "U1") (pin "5") (pinfunction "PA8_A4_D4_SDA_5") (pintype "bidirectional"))
      (node (ref "U2") (pin "23") (pinfunction "SDA_23") (pintype "bidirectional"))
      (node (ref "VL1") (pin "SDA") (pinfunction "SDA_SDA") (pintype "bidirectional"))
      (node (ref "VL10") (pin "SDA") (pinfunction "SDA_SDA") (pintype "bidirectional"))
      (node (ref "VL11") (pin "SDA") (pinfunction "SDA_SDA") (pintype "bidirectional"))
      (node (ref "VL12") (pin "SDA") (pinfunction "SDA_SDA") (pintype "bidirectional"))
      (node (ref "VL13") (pin "SDA") (pinfunction "SDA_SDA") (pintype "bidirectional"))
      (node (ref "VL14") (pin "SDA") (pinfunction "SDA_SDA") (pintype "bidirectional"))
      (node (ref "VL15") (pin "SDA") (pinfunction "SDA_SDA") (pintype "bidirectional"))
      (node (ref "VL16") (pin "SDA") (pinfunction "SDA_SDA") (pintype "bidirectional"))
      (node (ref "VL2") (pin "SDA") (pinfunction "SDA_SDA") (pintype "bidirectional"))
      (node (ref "VL3") (pin "SDA") (pinfunction "SDA_SDA") (pintype "bidirectional"))
      (node (ref "VL4") (pin "SDA") (pinfunction "SDA_SDA") (pintype "bidirectional"))
      (node (ref "VL5") (pin "SDA") (pinfunction "SDA_SDA") (pintype "bidirectional"))
      (node (ref "VL6") (pin "SDA") (pinfunction "SDA_SDA") (pintype "bidirectional"))
      (node (ref "VL7") (pin "SDA") (pinfunction "SDA_SDA") (pintype "bidirectional"))
      (node (ref "VL8") (pin "SDA") (pinfunction "SDA_SDA") (pintype "bidirectional"))
      (node (ref "VL9") (pin "SDA") (pinfunction "SDA_SDA") (pintype "bidirectional"))
    )
    (net (code "42") (name "TX") (class "Default")
      (node (ref "TP4") (pin "TP") (pinfunction "TP_TP") (pintype "input"))
      (node (ref "U1") (pin "7") (pinfunction "PB08_A6_D6_TX_7") (pintype "bidirectional"))
    )
    (net (code "43") (name "VDD") (class "Default")
      (node (ref "C2") (pin "1") (pinfunction "1_1") (pintype "passive"))
      (node (ref "C4") (pin "+") (pinfunction "+_+") (pintype "passive"))
      (node (ref "D1") (pin "K") (pinfunction "C_K") (pintype "passive"))
      (node (ref "REG1") (pin "1") (pinfunction "VIN_1") (pintype "passive"))
      (node (ref "TP1") (pin "TP") (pinfunction "TP_TP") (pintype "input"))
    )
    (net (code "44") (name "X1") (class "Default")
      (node (ref "R6") (pin "2") (pinfunction "2_2") (pintype "passive"))
      (node (ref "U2") (pin "6") (pinfunction "IO0_2_6") (pintype "bidirectional"))
      (node (ref "VL1") (pin "X") (pinfunction "XSHUT_X") (pintype "bidirectional"))
    )
    (net (code "45") (name "X2") (class "Default")
      (node (ref "R7") (pin "2") (pinfunction "2_2") (pintype "passive"))
      (node (ref "U2") (pin "5") (pinfunction "IO0_1_5") (pintype "bidirectional"))
      (node (ref "VL2") (pin "X") (pinfunction "XSHUT_X") (pintype "bidirectional"))
    )
    (net (code "46") (name "X3") (class "Default")
      (node (ref "R8") (pin "2") (pinfunction "2_2") (pintype "passive"))
      (node (ref "U2") (pin "4") (pinfunction "IO0_0_4") (pintype "bidirectional"))
      (node (ref "VL3") (pin "X") (pinfunction "XSHUT_X") (pintype "bidirectional"))
    )
    (net (code "47") (name "X4") (class "Default")
      (node (ref "R9") (pin "2") (pinfunction "2_2") (pintype "passive"))
      (node (ref "U2") (pin "20") (pinfunction "IO1_7_20") (pintype "bidirectional"))
      (node (ref "VL4") (pin "X") (pinfunction "XSHUT_X") (pintype "bidirectional"))
    )
    (net (code "48") (name "X5") (class "Default")
      (node (ref "R10") (pin "2") (pinfunction "2_2") (pintype "passive"))
      (node (ref "U2") (pin "19") (pinfunction "IO1_6_19") (pintype "bidirectional"))
      (node (ref "VL5") (pin "X") (pinfunction "XSHUT_X") (pintype "bidirectional"))
    )
    (net (code "49") (name "X6") (class "Default")
      (node (ref "R11") (pin "2") (pinfunction "2_2") (pintype "passive"))
      (node (ref "U2") (pin "18") (pinfunction "IO1_5_18") (pintype "bidirectional"))
      (node (ref "VL6") (pin "X") (pinfunction "XSHUT_X") (pintype "bidirectional"))
    )
    (net (code "50") (name "X7") (class "Default")
      (node (ref "R12") (pin "2") (pinfunction "2_2") (pintype "passive"))
      (node (ref "U2") (pin "17") (pinfunction "IO1_4_17") (pintype "bidirectional"))
      (node (ref "VL7") (pin "X") (pinfunction "XSHUT_X") (pintype "bidirectional"))
    )
    (net (code "51") (name "X8") (class "Default")
      (node (ref "R13") (pin "2") (pinfunction "2_2") (pintype "passive"))
      (node (ref "U2") (pin "16") (pinfunction "IO1_3_16") (pintype "bidirectional"))
      (node (ref "VL8") (pin "X") (pinfunction "XSHUT_X") (pintype "bidirectional"))
    )
    (net (code "52") (name "X9") (class "Default")
      (node (ref "R14") (pin "2") (pinfunction "2_2") (pintype "passive"))
      (node (ref "U2") (pin "15") (pinfunction "IO1_2_15") (pintype "bidirectional"))
      (node (ref "VL9") (pin "X") (pinfunction "XSHUT_X") (pintype "bidirectional"))
    )
    (net (code "53") (name "X10") (class "Default")
      (node (ref "R15") (pin "2") (pinfunction "2_2") (pintype "passive"))
      (node (ref "U2") (pin "14") (pinfunction "IO1_1_14") (pintype "bidirectional"))
      (node (ref "VL10") (pin "X") (pinfunction "XSHUT_X") (pintype "bidirectional"))
    )
    (net (code "54") (name "X11") (class "Default")
      (node (ref "R16") (pin "2") (pinfunction "2_2") (pintype "passive"))
      (node (ref "U2") (pin "8") (pinfunction "IO0_4_8") (pintype "bidirectional"))
      (node (ref "VL11") (pin "X") (pinfunction "XSHUT_X") (pintype "bidirectional"))
    )
    (net (code "55") (name "X12") (class "Default")
      (node (ref "R17") (pin "2") (pinfunction "2_2") (pintype "passive"))
      (node (ref "U2") (pin "7") (pinfunction "IO0_3_7") (pintype "bidirectional"))
      (node (ref "VL12") (pin "X") (pinfunction "XSHUT_X") (pintype "bidirectional"))
    )
    (net (code "56") (name "X13") (class "Default")
      (node (ref "R18") (pin "2") (pinfunction "2_2") (pintype "passive"))
      (node (ref "U2") (pin "9") (pinfunction "IO0_5_9") (pintype "bidirectional"))
      (node (ref "VL13") (pin "X") (pinfunction "XSHUT_X") (pintype "bidirectional"))
    )
    (net (code "57") (name "X14") (class "Default")
      (node (ref "R19") (pin "2") (pinfunction "2_2") (pintype "passive"))
      (node (ref "U2") (pin "10") (pinfunction "IO0_6_10") (pintype "bidirectional"))
      (node (ref "VL14") (pin "X") (pinfunction "XSHUT_X") (pintype "bidirectional"))
    )
    (net (code "58") (name "X15") (class "Default")
      (node (ref "R20") (pin "2") (pinfunction "2_2") (pintype "passive"))
      (node (ref "U2") (pin "11") (pinfunction "IO0_7_11") (pintype "bidirectional"))
      (node (ref "VL15") (pin "X") (pinfunction "XSHUT_X") (pintype "bidirectional"))
    )
    (net (code "59") (name "X16") (class "Default")
      (node (ref "R21") (pin "2") (pinfunction "2_2") (pintype "passive"))
      (node (ref "U2") (pin "13") (pinfunction "IO1_0_13") (pintype "bidirectional"))
      (node (ref "VL16") (pin "X") (pinfunction "XSHUT_X") (pintype "bidirectional"))
    )
    (net (code "60") (name "unconnected-(LED32-DO-Pad2-DOUT)") (class "Default")
      (node (ref "LED32") (pin "2-DOUT") (pinfunction "DO_2-DOUT") (pintype "output"))
    )
    (net (code "61") (name "unconnected-(U1-PA02_A0_D0-Pad1)") (class "Default")
      (node (ref "U1") (pin "1") (pinfunction "PA02_A0_D0_1") (pintype "bidirectional"))
    )
    (net (code "62") (name "unconnected-(U1-PA4_A1_D1-Pad2)") (class "Default")
      (node (ref "U1") (pin "2") (pinfunction "PA4_A1_D1_2") (pintype "bidirectional"))
    )
    (net (code "63") (name "unconnected-(U1-PA5_A9_D9_MISO-Pad10)") (class "Default")
      (node (ref "U1") (pin "10") (pinfunction "PA5_A9_D9_MISO_10") (pintype "bidirectional"))
    )
    (net (code "64") (name "unconnected-(U1-PA6_A10_D10_MOSI-Pad11)") (class "Default")
      (node (ref "U1") (pin "11") (pinfunction "PA6_A10_D10_MOSI_11") (pintype "bidirectional"))
    )
    (net (code "65") (name "unconnected-(U1-PA7_A8_D8_SCK-Pad9)") (class "Default")
      (node (ref "U1") (pin "9") (pinfunction "PA7_A8_D8_SCK_9") (pintype "bidirectional"))
    )
    (net (code "66") (name "unconnected-(U1-PA10_A2_D2-Pad3)") (class "Default")
      (node (ref "U1") (pin "3") (pinfunction "PA10_A2_D2_3") (pintype "bidirectional"))
    )
    (net (code "67") (name "unconnected-(U1-PA11_A3_D3-Pad4)") (class "Default")
      (node (ref "U1") (pin "4") (pinfunction "PA11_A3_D3_4") (pintype "bidirectional"))
    )
    (net (code "68") (name "unconnected-(VL1-GPIO-PadG)") (class "Default")
      (node (ref "VL1") (pin "G") (pinfunction "GPIO_G") (pintype "bidirectional"))
    )
    (net (code "69") (name "unconnected-(VL2-GPIO-PadG)") (class "Default")
      (node (ref "VL2") (pin "G") (pinfunction "GPIO_G") (pintype "bidirectional"))
    )
    (net (code "70") (name "unconnected-(VL3-GPIO-PadG)") (class "Default")
      (node (ref "VL3") (pin "G") (pinfunction "GPIO_G") (pintype "bidirectional"))
    )
    (net (code "71") (name "unconnected-(VL4-GPIO-PadG)") (class "Default")
      (node (ref "VL4") (pin "G") (pinfunction "GPIO_G") (pintype "bidirectional"))
    )
    (net (code "72") (name "unconnected-(VL5-GPIO-PadG)") (class "Default")
      (node (ref "VL5") (pin "G") (pinfunction "GPIO_G") (pintype "bidirectional"))
    )
    (net (code "73") (name "unconnected-(VL6-GPIO-PadG)") (class "Default")
      (node (ref "VL6") (pin "G") (pinfunction "GPIO_G") (pintype "bidirectional"))
    )
    (net (code "74") (name "unconnected-(VL7-GPIO-PadG)") (class "Default")
      (node (ref "VL7") (pin "G") (pinfunction "GPIO_G") (pintype "bidirectional"))
    )
    (net (code "75") (name "unconnected-(VL8-GPIO-PadG)") (class "Default")
      (node (ref "VL8") (pin "G") (pinfunction "GPIO_G") (pintype "bidirectional"))
    )
    (net (code "76") (name "unconnected-(VL9-GPIO-PadG)") (class "Default")
      (node (ref "VL9") (pin "G") (pinfunction "GPIO_G") (pintype "bidirectional"))
    )
    (net (code "77") (name "unconnected-(VL10-GPIO-PadG)") (class "Default")
      (node (ref "VL10") (pin "G") (pinfunction "GPIO_G") (pintype "bidirectional"))
    )
    (net (code "78") (name "unconnected-(VL11-GPIO-PadG)") (class "Default")
      (node (ref "VL11") (pin "G") (pinfunction "GPIO_G") (pintype "bidirectional"))
    )
    (net (code "79") (name "unconnected-(VL12-GPIO-PadG)") (class "Default")
      (node (ref "VL12") (pin "G") (pinfunction "GPIO_G") (pintype "bidirectional"))
    )
    (net (code "80") (name "unconnected-(VL13-GPIO-PadG)") (class "Default")
      (node (ref "VL13") (pin "G") (pinfunction "GPIO_G") (pintype "bidirectional"))
    )
    (net (code "81") (name "unconnected-(VL14-GPIO-PadG)") (class "Default")
      (node (ref "VL14") (pin "G") (pinfunction "GPIO_G") (pintype "bidirectional"))
    )
    (net (code "82") (name "unconnected-(VL15-GPIO-PadG)") (class "Default")
      (node (ref "VL15") (pin "G") (pinfunction "GPIO_G") (pintype "bidirectional"))
    )
    (net (code "83") (name "unconnected-(VL16-GPIO-PadG)") (class "Default")
      (node (ref "VL16") (pin "G") (pinfunction "GPIO_G") (pintype "bidirectional"))
    )
  )
)
